# Ocreeb_12.net
KiCad netlist of a schematic drawn in EAGLE
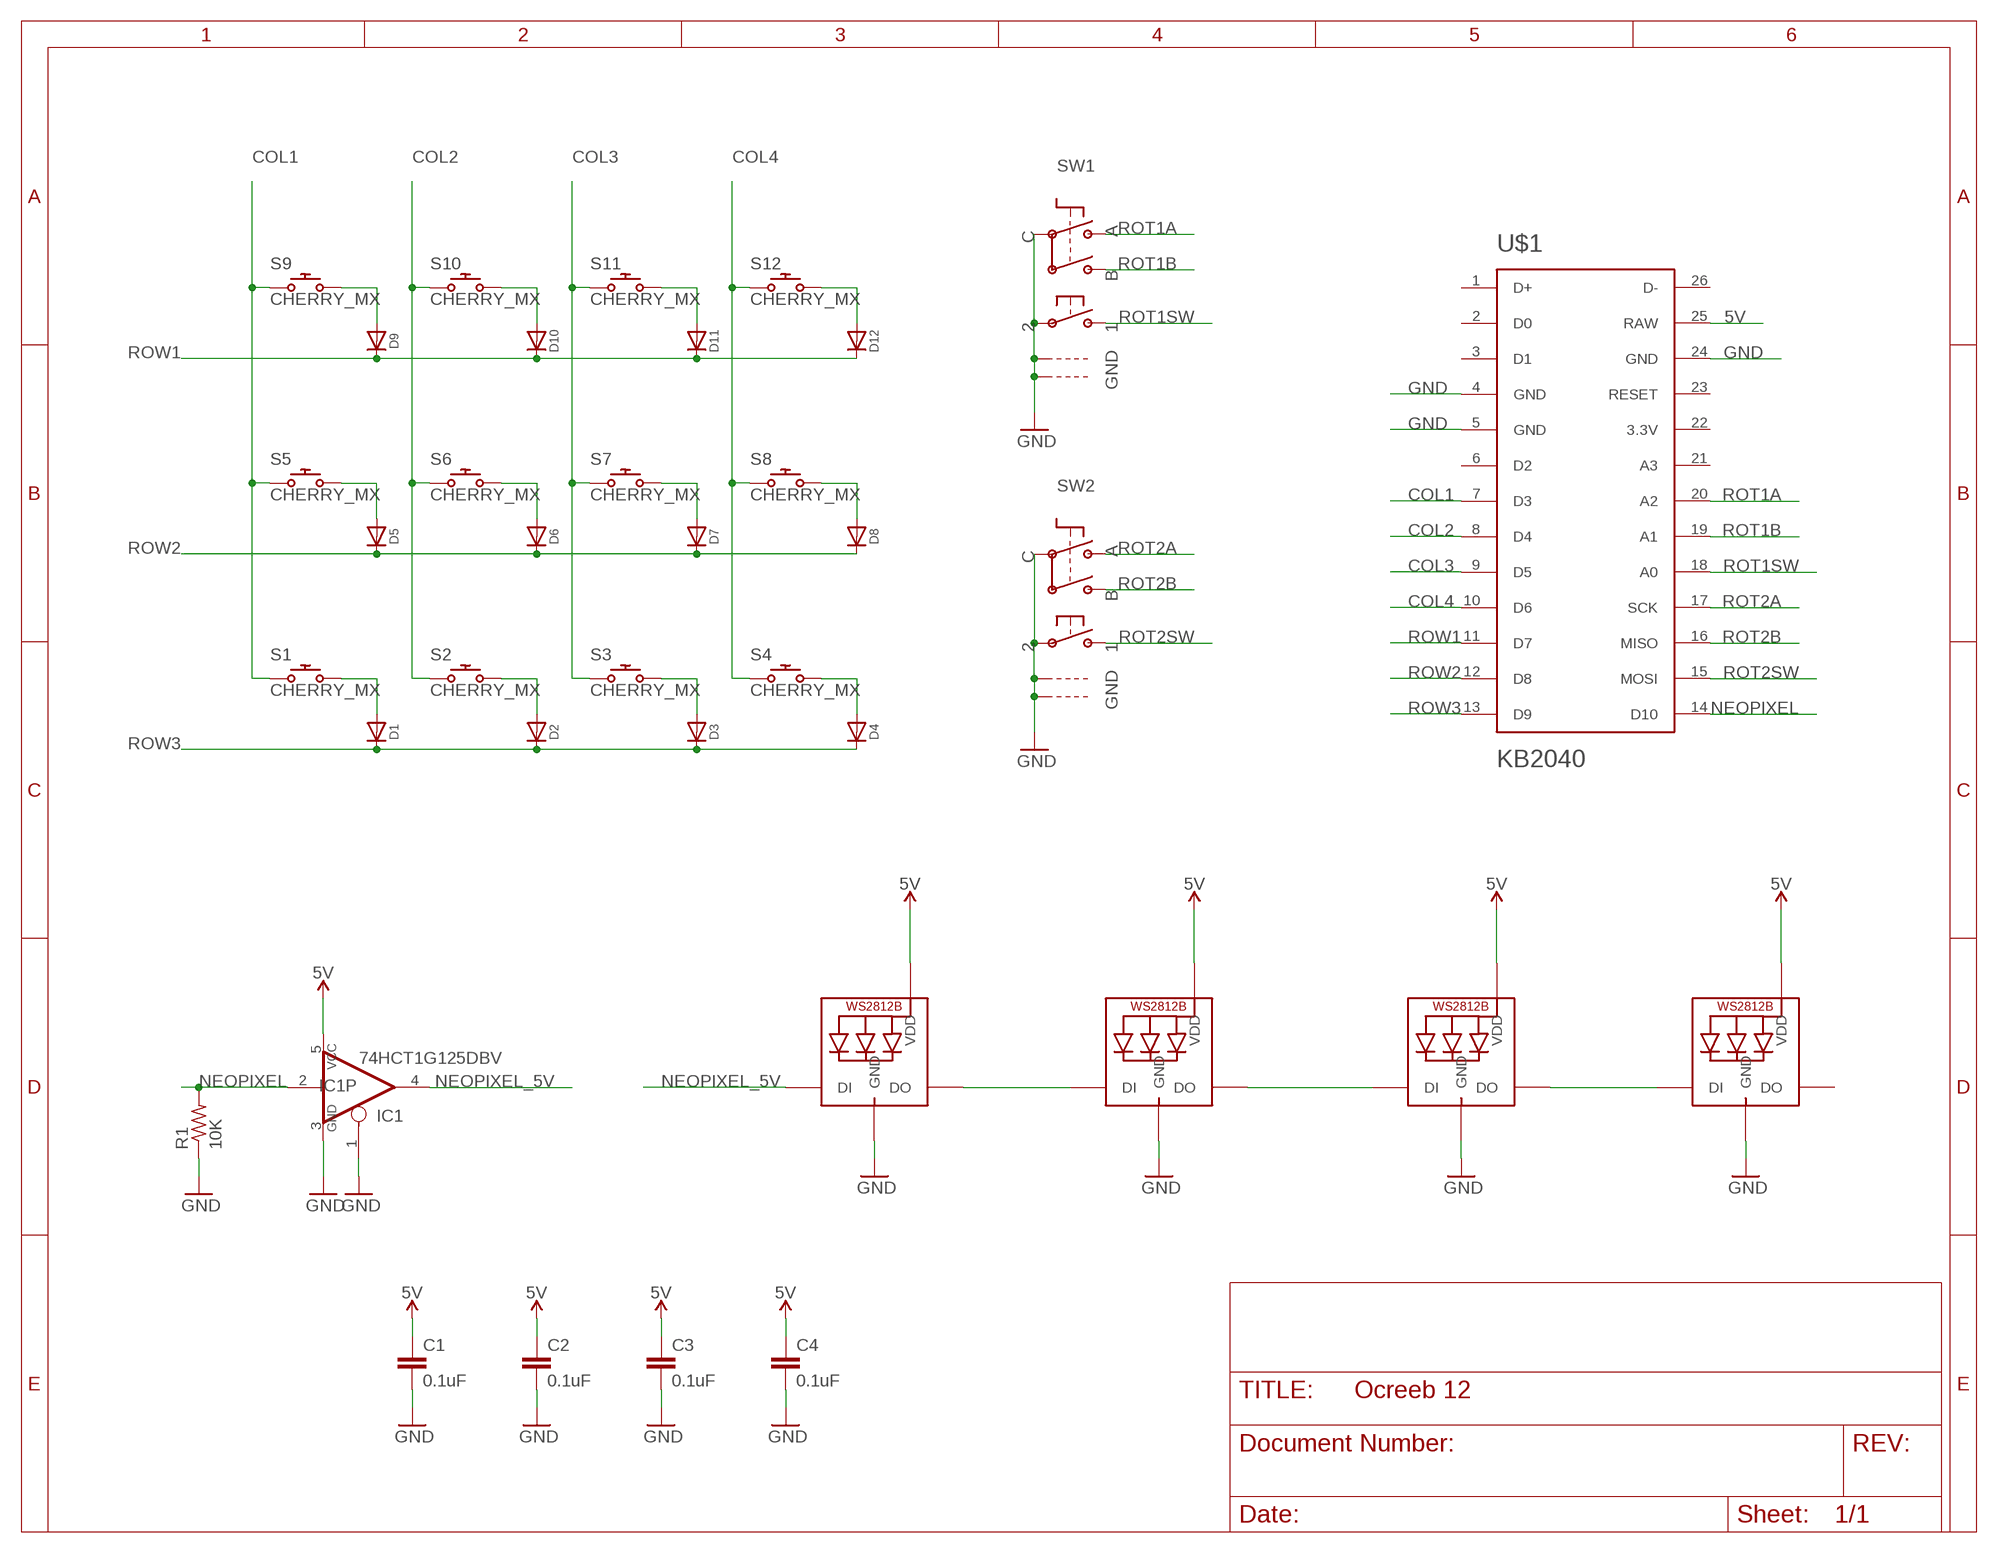
[diagram p0: schematic, sheet 1]

(export (version "E")
  (design (tool "Eeschema 10.0.6"))
  (components
    (comp (ref "C1")
      (value "0.1uF")
      (footprint "eagle-import:0603")
      (libsource (lib "eagle-import") (part "0.1UF-0603-25V-(+80/-20%)"))
    )
    (comp (ref "C2")
      (value "0.1uF")
      (footprint "eagle-import:0603")
      (libsource (lib "eagle-import") (part "0.1UF-0603-25V-(+80/-20%)"))
    )
    (comp (ref "C3")
      (value "0.1uF")
      (footprint "eagle-import:0603")
      (libsource (lib "eagle-import") (part "0.1UF-0603-25V-(+80/-20%)"))
    )
    (comp (ref "C4")
      (value "0.1uF")
      (footprint "eagle-import:0603")
      (libsource (lib "eagle-import") (part "0.1UF-0603-25V-(+80/-20%)"))
    )
    (comp (ref "D1")
      (value "MICROBUILDER_DIODESOD-123")
      (footprint "eagle-import:MICROBUILDER_SOD-123")
      (libsource (lib "eagle-import") (part "MICROBUILDER_DIODESOD-123"))
    )
    (comp (ref "D2")
      (value "MICROBUILDER_DIODESOD-123")
      (footprint "eagle-import:MICROBUILDER_SOD-123")
      (libsource (lib "eagle-import") (part "MICROBUILDER_DIODESOD-123"))
    )
    (comp (ref "D3")
      (value "MICROBUILDER_DIODESOD-123")
      (footprint "eagle-import:MICROBUILDER_SOD-123")
      (libsource (lib "eagle-import") (part "MICROBUILDER_DIODESOD-123"))
    )
    (comp (ref "D4")
      (value "MICROBUILDER_DIODESOD-123")
      (footprint "eagle-import:MICROBUILDER_SOD-123")
      (libsource (lib "eagle-import") (part "MICROBUILDER_DIODESOD-123"))
    )
    (comp (ref "D5")
      (value "MICROBUILDER_DIODESOD-123")
      (footprint "eagle-import:MICROBUILDER_SOD-123")
      (libsource (lib "eagle-import") (part "MICROBUILDER_DIODESOD-123"))
    )
    (comp (ref "D6")
      (value "MICROBUILDER_DIODESOD-123")
      (footprint "eagle-import:MICROBUILDER_SOD-123")
      (libsource (lib "eagle-import") (part "MICROBUILDER_DIODESOD-123"))
    )
    (comp (ref "D7")
      (value "MICROBUILDER_DIODESOD-123")
      (footprint "eagle-import:MICROBUILDER_SOD-123")
      (libsource (lib "eagle-import") (part "MICROBUILDER_DIODESOD-123"))
    )
    (comp (ref "D8")
      (value "MICROBUILDER_DIODESOD-123")
      (footprint "eagle-import:MICROBUILDER_SOD-123")
      (libsource (lib "eagle-import") (part "MICROBUILDER_DIODESOD-123"))
    )
    (comp (ref "D9")
      (value "MICROBUILDER_DIODESOD-123")
      (footprint "eagle-import:MICROBUILDER_SOD-123")
      (libsource (lib "eagle-import") (part "MICROBUILDER_DIODESOD-123"))
    )
    (comp (ref "D10")
      (value "MICROBUILDER_DIODESOD-123")
      (footprint "eagle-import:MICROBUILDER_SOD-123")
      (libsource (lib "eagle-import") (part "MICROBUILDER_DIODESOD-123"))
    )
    (comp (ref "D11")
      (value "MICROBUILDER_DIODESOD-123")
      (footprint "eagle-import:MICROBUILDER_SOD-123")
      (libsource (lib "eagle-import") (part "MICROBUILDER_DIODESOD-123"))
    )
    (comp (ref "D12")
      (value "MICROBUILDER_DIODESOD-123")
      (footprint "eagle-import:MICROBUILDER_SOD-123")
      (libsource (lib "eagle-import") (part "MICROBUILDER_DIODESOD-123"))
    )
    (comp (ref "IC1")
      (value "74HCT1G125DBV")
      (footprint "eagle-import:SOT23-5")
      (libsource (lib "eagle-import") (part "741G125DBVAHC"))
    )
    (comp (ref "LED1")
      (value "WS2812B5050")
      (footprint "eagle-import:WS2812B")
      (libsource (lib "eagle-import") (part "WS2812B5050"))
    )
    (comp (ref "LED2")
      (value "WS2812B5050")
      (footprint "eagle-import:WS2812B")
      (libsource (lib "eagle-import") (part "WS2812B5050"))
    )
    (comp (ref "LED3")
      (value "WS2812B5050")
      (footprint "eagle-import:WS2812B")
      (libsource (lib "eagle-import") (part "WS2812B5050"))
    )
    (comp (ref "LED4")
      (value "WS2812B5050")
      (footprint "eagle-import:WS2812B")
      (libsource (lib "eagle-import") (part "WS2812B5050"))
    )
    (comp (ref "R1")
      (value "10K")
      (footprint "eagle-import:R0805")
      (libsource (lib "eagle-import") (part "R-US_R0805"))
    )
    (comp (ref "S1")
      (value "CHERRY_MX")
      (footprint "eagle-import:CHERRY_MX")
      (libsource (lib "eagle-import") (part "CHERRY_MX"))
    )
    (comp (ref "S2")
      (value "CHERRY_MX")
      (footprint "eagle-import:CHERRY_MX")
      (libsource (lib "eagle-import") (part "CHERRY_MX"))
    )
    (comp (ref "S3")
      (value "CHERRY_MX")
      (footprint "eagle-import:CHERRY_MX")
      (libsource (lib "eagle-import") (part "CHERRY_MX"))
    )
    (comp (ref "S4")
      (value "CHERRY_MX")
      (footprint "eagle-import:CHERRY_MX")
      (libsource (lib "eagle-import") (part "CHERRY_MX"))
    )
    (comp (ref "S5")
      (value "CHERRY_MX")
      (footprint "eagle-import:CHERRY_MX")
      (libsource (lib "eagle-import") (part "CHERRY_MX"))
    )
    (comp (ref "S6")
      (value "CHERRY_MX")
      (footprint "eagle-import:CHERRY_MX")
      (libsource (lib "eagle-import") (part "CHERRY_MX"))
    )
    (comp (ref "S7")
      (value "CHERRY_MX")
      (footprint "eagle-import:CHERRY_MX")
      (libsource (lib "eagle-import") (part "CHERRY_MX"))
    )
    (comp (ref "S8")
      (value "CHERRY_MX")
      (footprint "eagle-import:CHERRY_MX")
      (libsource (lib "eagle-import") (part "CHERRY_MX"))
    )
    (comp (ref "S9")
      (value "CHERRY_MX")
      (footprint "eagle-import:CHERRY_MX")
      (libsource (lib "eagle-import") (part "CHERRY_MX"))
    )
    (comp (ref "S10")
      (value "CHERRY_MX")
      (footprint "eagle-import:CHERRY_MX")
      (libsource (lib "eagle-import") (part "CHERRY_MX"))
    )
    (comp (ref "S11")
      (value "CHERRY_MX")
      (footprint "eagle-import:CHERRY_MX")
      (libsource (lib "eagle-import") (part "CHERRY_MX"))
    )
    (comp (ref "S12")
      (value "CHERRY_MX")
      (footprint "eagle-import:CHERRY_MX")
      (libsource (lib "eagle-import") (part "CHERRY_MX"))
    )
    (comp (ref "SW1")
      (value "ADAFRUIT_ELECTROMECH_ENCODER_PLUS_SWITCH_BOURNS_PEC11")
      (footprint "eagle-import:ADAFRUIT_ELECTROMECH_PEC11+SWITCH")
      (libsource (lib "eagle-import") (part "ADAFRUIT_ELECTROMECH_ENCODER_PLUS_SWITCH_PEC11_BOURNS"))
    )
    (comp (ref "SW2")
      (value "ADAFRUIT_ELECTROMECH_ENCODER_PLUS_SWITCH_BOURNS_PEC11")
      (footprint "eagle-import:ADAFRUIT_ELECTROMECH_PEC11+SWITCH")
      (libsource (lib "eagle-import") (part "ADAFRUIT_ELECTROMECH_ENCODER_PLUS_SWITCH_PEC11_BOURNS"))
    )
    (comp (ref "U$1")
      (value "KB2040")
      (footprint "eagle-import:KB2040_SMD")
      (libsource (lib "eagle-import") (part "KB2040"))
    )
  )
  (nets
    (net (code "1") (name "/COL1") (class "Default")
      (node (ref "S1") (pin "S1") (pinfunction "1_S1") (pintype "passive"))
      (node (ref "S5") (pin "S1") (pinfunction "1_S1") (pintype "passive"))
      (node (ref "S9") (pin "S1") (pinfunction "1_S1") (pintype "passive"))
      (node (ref "U$1") (pin "7") (pinfunction "D3_7") (pintype "bidirectional"))
    )
    (net (code "2") (name "/COL2") (class "Default")
      (node (ref "S10") (pin "S1") (pinfunction "1_S1") (pintype "passive"))
      (node (ref "S2") (pin "S1") (pinfunction "1_S1") (pintype "passive"))
      (node (ref "S6") (pin "S1") (pinfunction "1_S1") (pintype "passive"))
      (node (ref "U$1") (pin "8") (pinfunction "D4_8") (pintype "bidirectional"))
    )
    (net (code "3") (name "/COL3") (class "Default")
      (node (ref "S11") (pin "S1") (pinfunction "1_S1") (pintype "passive"))
      (node (ref "S3") (pin "S1") (pinfunction "1_S1") (pintype "passive"))
      (node (ref "S7") (pin "S1") (pinfunction "1_S1") (pintype "passive"))
      (node (ref "U$1") (pin "9") (pinfunction "D5_9") (pintype "bidirectional"))
    )
    (net (code "4") (name "/COL4") (class "Default")
      (node (ref "S12") (pin "S1") (pinfunction "1_S1") (pintype "passive"))
      (node (ref "S4") (pin "S1") (pinfunction "1_S1") (pintype "passive"))
      (node (ref "S8") (pin "S1") (pinfunction "1_S1") (pintype "passive"))
      (node (ref "U$1") (pin "10") (pinfunction "D6_10") (pintype "bidirectional"))
    )
    (net (code "5") (name "/NEOPIXEL") (class "Default")
      (node (ref "IC1") (pin "2") (pinfunction "I_2") (pintype "input"))
      (node (ref "R1") (pin "2") (pinfunction "2_2") (pintype "passive"))
      (node (ref "U$1") (pin "14") (pinfunction "D10_14") (pintype "bidirectional"))
    )
    (net (code "6") (name "/NEOPIXEL_5V") (class "Default")
      (node (ref "IC1") (pin "4") (pinfunction "O_4") (pintype "tri_state"))
      (node (ref "LED1") (pin "4-DIN") (pinfunction "DI_4-DIN") (pintype "input"))
    )
    (net (code "7") (name "/ROT1A") (class "Default")
      (node (ref "SW1") (pin "P$A") (pinfunction "P$A_P$A") (pintype "passive"))
      (node (ref "U$1") (pin "20") (pinfunction "A2_20") (pintype "bidirectional"))
    )
    (net (code "8") (name "/ROT1B") (class "Default")
      (node (ref "SW1") (pin "P$B") (pinfunction "P$B_P$B") (pintype "passive"))
      (node (ref "U$1") (pin "19") (pinfunction "A1_19") (pintype "bidirectional"))
    )
    (net (code "9") (name "/ROT1SW") (class "Default")
      (node (ref "SW1") (pin "P$1") (pinfunction "P$1_P$1") (pintype "passive"))
      (node (ref "U$1") (pin "18") (pinfunction "A0_18") (pintype "bidirectional"))
    )
    (net (code "10") (name "/ROT2A") (class "Default")
      (node (ref "SW2") (pin "P$A") (pinfunction "P$A_P$A") (pintype "passive"))
      (node (ref "U$1") (pin "17") (pinfunction "SCK_17") (pintype "bidirectional"))
    )
    (net (code "11") (name "/ROT2B") (class "Default")
      (node (ref "SW2") (pin "P$B") (pinfunction "P$B_P$B") (pintype "passive"))
      (node (ref "U$1") (pin "16") (pinfunction "MISO_16") (pintype "bidirectional"))
    )
    (net (code "12") (name "/ROT2SW") (class "Default")
      (node (ref "SW2") (pin "P$1") (pinfunction "P$1_P$1") (pintype "passive"))
      (node (ref "U$1") (pin "15") (pinfunction "MOSI_15") (pintype "bidirectional"))
    )
    (net (code "13") (name "/ROW1") (class "Default")
      (node (ref "D10") (pin "C") (pinfunction "C_C") (pintype "passive"))
      (node (ref "D11") (pin "C") (pinfunction "C_C") (pintype "passive"))
      (node (ref "D12") (pin "C") (pinfunction "C_C") (pintype "passive"))
      (node (ref "D9") (pin "C") (pinfunction "C_C") (pintype "passive"))
      (node (ref "U$1") (pin "11") (pinfunction "D7_11") (pintype "bidirectional"))
    )
    (net (code "14") (name "/ROW2") (class "Default")
      (node (ref "D5") (pin "C") (pinfunction "C_C") (pintype "passive"))
      (node (ref "D6") (pin "C") (pinfunction "C_C") (pintype "passive"))
      (node (ref "D7") (pin "C") (pinfunction "C_C") (pintype "passive"))
      (node (ref "D8") (pin "C") (pinfunction "C_C") (pintype "passive"))
      (node (ref "U$1") (pin "12") (pinfunction "D8_12") (pintype "bidirectional"))
    )
    (net (code "15") (name "/ROW3") (class "Default")
      (node (ref "D1") (pin "C") (pinfunction "C_C") (pintype "passive"))
      (node (ref "D2") (pin "C") (pinfunction "C_C") (pintype "passive"))
      (node (ref "D3") (pin "C") (pinfunction "C_C") (pintype "passive"))
      (node (ref "D4") (pin "C") (pinfunction "C_C") (pintype "passive"))
      (node (ref "U$1") (pin "13") (pinfunction "D9_13") (pintype "bidirectional"))
    )
    (net (code "16") (name "5V") (class "Default")
      (node (ref "C1") (pin "1") (pinfunction "1_1") (pintype "passive"))
      (node (ref "C2") (pin "1") (pinfunction "1_1") (pintype "passive"))
      (node (ref "C3") (pin "1") (pinfunction "1_1") (pintype "passive"))
      (node (ref "C4") (pin "1") (pinfunction "1_1") (pintype "passive"))
      (node (ref "IC1") (pin "5") (pinfunction "VCC_5") (pintype "power_in"))
      (node (ref "LED1") (pin "1-VDD") (pinfunction "VDD_1-VDD") (pintype "power_in"))
      (node (ref "LED2") (pin "1-VDD") (pinfunction "VDD_1-VDD") (pintype "power_in"))
      (node (ref "LED3") (pin "1-VDD") (pinfunction "VDD_1-VDD") (pintype "power_in"))
      (node (ref "LED4") (pin "1-VDD") (pinfunction "VDD_1-VDD") (pintype "power_in"))
      (node (ref "U$1") (pin "25") (pinfunction "RAW_25") (pintype "bidirectional"))
    )
    (net (code "17") (name "GND") (class "Default")
      (node (ref "C1") (pin "2") (pinfunction "2_2") (pintype "passive"))
      (node (ref "C2") (pin "2") (pinfunction "2_2") (pintype "passive"))
      (node (ref "C3") (pin "2") (pinfunction "2_2") (pintype "passive"))
      (node (ref "C4") (pin "2") (pinfunction "2_2") (pintype "passive"))
      (node (ref "IC1") (pin "1") (pinfunction "OE_1") (pintype "input"))
      (node (ref "IC1") (pin "3") (pinfunction "GND_3") (pintype "power_in"))
      (node (ref "LED1") (pin "3-GND") (pinfunction "GND_3-GND") (pintype "power_in"))
      (node (ref "LED2") (pin "3-GND") (pinfunction "GND_3-GND") (pintype "power_in"))
      (node (ref "LED3") (pin "3-GND") (pinfunction "GND_3-GND") (pintype "power_in"))
      (node (ref "LED4") (pin "3-GND") (pinfunction "GND_3-GND") (pintype "power_in"))
      (node (ref "R1") (pin "1") (pinfunction "1_1") (pintype "passive"))
      (node (ref "SW1") (pin "P$2") (pinfunction "P$2_P$2") (pintype "passive"))
      (node (ref "SW1") (pin "P$C") (pinfunction "P$C_P$C") (pintype "passive"))
      (node (ref "SW1") (pin "P$GND1") (pinfunction "P$GND1_P$GND1") (pintype "passive"))
      (node (ref "SW1") (pin "P$GND2") (pinfunction "P$GND2_P$GND2") (pintype "passive"))
      (node (ref "SW2") (pin "P$2") (pinfunction "P$2_P$2") (pintype "passive"))
      (node (ref "SW2") (pin "P$C") (pinfunction "P$C_P$C") (pintype "passive"))
      (node (ref "SW2") (pin "P$GND1") (pinfunction "P$GND1_P$GND1") (pintype "passive"))
      (node (ref "SW2") (pin "P$GND2") (pinfunction "P$GND2_P$GND2") (pintype "passive"))
      (node (ref "U$1") (pin "24") (pinfunction "GND_24") (pintype "bidirectional"))
      (node (ref "U$1") (pin "4") (pinfunction "GND_4") (pintype "bidirectional"))
      (node (ref "U$1") (pin "5") (pinfunction "GND_5") (pintype "bidirectional"))
    )
    (net (code "18") (name "Net-(LED1-DO)") (class "Default")
      (node (ref "LED1") (pin "2-DOUT") (pinfunction "DO_2-DOUT") (pintype "output"))
      (node (ref "LED2") (pin "4-DIN") (pinfunction "DI_4-DIN") (pintype "input"))
    )
    (net (code "19") (name "Net-(LED2-DO)") (class "Default")
      (node (ref "LED2") (pin "2-DOUT") (pinfunction "DO_2-DOUT") (pintype "output"))
      (node (ref "LED3") (pin "4-DIN") (pinfunction "DI_4-DIN") (pintype "input"))
    )
    (net (code "20") (name "Net-(LED3-DO)") (class "Default")
      (node (ref "LED3") (pin "2-DOUT") (pinfunction "DO_2-DOUT") (pintype "output"))
      (node (ref "LED4") (pin "4-DIN") (pinfunction "DI_4-DIN") (pintype "input"))
    )
    (net (code "21") (name "Net-(S1-2)") (class "Default")
      (node (ref "D1") (pin "A") (pinfunction "A_A") (pintype "passive"))
      (node (ref "S1") (pin "S2") (pinfunction "2_S2") (pintype "passive"))
    )
    (net (code "22") (name "Net-(S2-2)") (class "Default")
      (node (ref "D2") (pin "A") (pinfunction "A_A") (pintype "passive"))
      (node (ref "S2") (pin "S2") (pinfunction "2_S2") (pintype "passive"))
    )
    (net (code "23") (name "Net-(S3-2)") (class "Default")
      (node (ref "D3") (pin "A") (pinfunction "A_A") (pintype "passive"))
      (node (ref "S3") (pin "S2") (pinfunction "2_S2") (pintype "passive"))
    )
    (net (code "24") (name "Net-(S4-2)") (class "Default")
      (node (ref "D4") (pin "A") (pinfunction "A_A") (pintype "passive"))
      (node (ref "S4") (pin "S2") (pinfunction "2_S2") (pintype "passive"))
    )
    (net (code "25") (name "Net-(S5-2)") (class "Default")
      (node (ref "D5") (pin "A") (pinfunction "A_A") (pintype "passive"))
      (node (ref "S5") (pin "S2") (pinfunction "2_S2") (pintype "passive"))
    )
    (net (code "26") (name "Net-(S6-2)") (class "Default")
      (node (ref "D6") (pin "A") (pinfunction "A_A") (pintype "passive"))
      (node (ref "S6") (pin "S2") (pinfunction "2_S2") (pintype "passive"))
    )
    (net (code "27") (name "Net-(S7-2)") (class "Default")
      (node (ref "D7") (pin "A") (pinfunction "A_A") (pintype "passive"))
      (node (ref "S7") (pin "S2") (pinfunction "2_S2") (pintype "passive"))
    )
    (net (code "28") (name "Net-(S8-2)") (class "Default")
      (node (ref "D8") (pin "A") (pinfunction "A_A") (pintype "passive"))
      (node (ref "S8") (pin "S2") (pinfunction "2_S2") (pintype "passive"))
    )
    (net (code "29") (name "Net-(S9-2)") (class "Default")
      (node (ref "D9") (pin "A") (pinfunction "A_A") (pintype "passive"))
      (node (ref "S9") (pin "S2") (pinfunction "2_S2") (pintype "passive"))
    )
    (net (code "30") (name "Net-(S10-2)") (class "Default")
      (node (ref "D10") (pin "A") (pinfunction "A_A") (pintype "passive"))
      (node (ref "S10") (pin "S2") (pinfunction "2_S2") (pintype "passive"))
    )
    (net (code "31") (name "Net-(S11-2)") (class "Default")
      (node (ref "D11") (pin "A") (pinfunction "A_A") (pintype "passive"))
      (node (ref "S11") (pin "S2") (pinfunction "2_S2") (pintype "passive"))
    )
    (net (code "32") (name "Net-(S12-2)") (class "Default")
      (node (ref "D12") (pin "A") (pinfunction "A_A") (pintype "passive"))
      (node (ref "S12") (pin "S2") (pinfunction "2_S2") (pintype "passive"))
    )
    (net (code "33") (name "unconnected-(LED4-DO-Pad2-DOUT)") (class "Default")
      (node (ref "LED4") (pin "2-DOUT") (pinfunction "DO_2-DOUT") (pintype "output"))
    )
    (net (code "34") (name "unconnected-(U$1-3.3V-Pad22)") (class "Default")
      (node (ref "U$1") (pin "22") (pinfunction "3.3V_22") (pintype "bidirectional"))
    )
    (net (code "35") (name "unconnected-(U$1-A3-Pad21)") (class "Default")
      (node (ref "U$1") (pin "21") (pinfunction "A3_21") (pintype "bidirectional"))
    )
    (net (code "36") (name "unconnected-(U$1-D+-Pad1)") (class "Default")
      (node (ref "U$1") (pin "1") (pinfunction "D+_1") (pintype "bidirectional"))
    )
    (net (code "37") (name "unconnected-(U$1-D--Pad26)") (class "Default")
      (node (ref "U$1") (pin "26") (pinfunction "D-_26") (pintype "bidirectional"))
    )
    (net (code "38") (name "unconnected-(U$1-D0-Pad2)") (class "Default")
      (node (ref "U$1") (pin "2") (pinfunction "D0_2") (pintype "bidirectional"))
    )
    (net (code "39") (name "unconnected-(U$1-D1-Pad3)") (class "Default")
      (node (ref "U$1") (pin "3") (pinfunction "D1_3") (pintype "bidirectional"))
    )
    (net (code "40") (name "unconnected-(U$1-D2-Pad6)") (class "Default")
      (node (ref "U$1") (pin "6") (pinfunction "D2_6") (pintype "bidirectional"))
    )
    (net (code "41") (name "unconnected-(U$1-RESET-Pad23)") (class "Default")
      (node (ref "U$1") (pin "23") (pinfunction "RESET_23") (pintype "bidirectional"))
    )
  )
)
